# v2.net
KiCad netlist of a schematic drawn in EAGLE
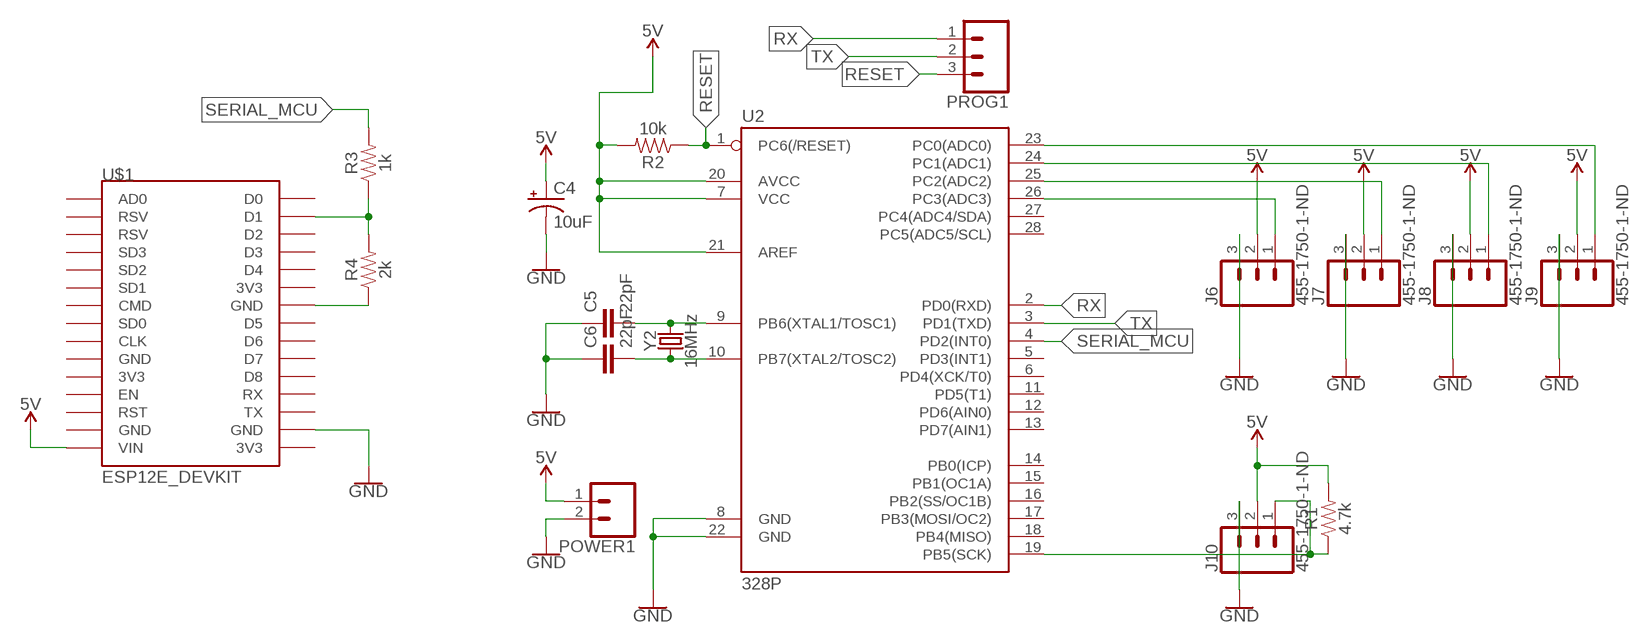
[diagram p0: schematic, sheet 1]

(export (version "E")
  (design (tool "Eeschema 10.0.6"))
  (components
    (comp (ref "C4")
      (value "10uF")
      (footprint "eagle-import:CPOL-RADIAL-2.5MM-5MM")
      (libsource (lib "eagle-import") (part "10UF-POLAR-RADIAL-2.5MM-25V-20%"))
    )
    (comp (ref "C5")
      (value "22pF")
      (footprint "eagle-import:CAP-PTH-2.54")
      (libsource (lib "eagle-import") (part "22PF-PTH-2.54MM-200V-5%"))
    )
    (comp (ref "C6")
      (value "22pF")
      (footprint "eagle-import:CAP-PTH-2.54")
      (libsource (lib "eagle-import") (part "22PF-PTH-2.54MM-200V-5%"))
    )
    (comp (ref "J6")
      (value "455-1750-1-ND")
      (footprint "eagle-import:1X03")
      (libsource (lib "eagle-import") (part "CONN_03"))
    )
    (comp (ref "J7")
      (value "455-1750-1-ND")
      (footprint "eagle-import:1X03")
      (libsource (lib "eagle-import") (part "CONN_03"))
    )
    (comp (ref "J8")
      (value "455-1750-1-ND")
      (footprint "eagle-import:1X03")
      (libsource (lib "eagle-import") (part "CONN_03"))
    )
    (comp (ref "J9")
      (value "455-1750-1-ND")
      (footprint "eagle-import:1X03")
      (libsource (lib "eagle-import") (part "CONN_03"))
    )
    (comp (ref "J10")
      (value "455-1750-1-ND")
      (footprint "eagle-import:1X03")
      (libsource (lib "eagle-import") (part "CONN_03"))
    )
    (comp (ref "POWER1")
      (value "CONN_02")
      (footprint "eagle-import:1X02")
      (libsource (lib "eagle-import") (part "CONN_02"))
    )
    (comp (ref "PROG1")
      (value "CONN_03")
      (footprint "eagle-import:1X03")
      (libsource (lib "eagle-import") (part "SparkFun-Connectors_513_CONN_03"))
    )
    (comp (ref "R1")
      (value "4.7k")
      (footprint "eagle-import:AXIAL-0.3")
      (libsource (lib "eagle-import") (part "10KOHM-HORIZ-1/4W-1%"))
    )
    (comp (ref "R2")
      (value "10k")
      (footprint "eagle-import:AXIAL-0.3")
      (libsource (lib "eagle-import") (part "1KOHM-HORIZ-1/4W-1%"))
    )
    (comp (ref "R3")
      (value "1k")
      (footprint "eagle-import:AXIAL-0.3")
      (libsource (lib "eagle-import") (part "10KOHM-HORIZ-1/4W-1%"))
    )
    (comp (ref "R4")
      (value "2k")
      (footprint "eagle-import:AXIAL-0.3")
      (libsource (lib "eagle-import") (part "10KOHM-HORIZ-1/4W-1%"))
    )
    (comp (ref "U$1")
      (value "ESP12E_DEVKIT")
      (footprint "eagle-import:ESP12E_DEVKIT")
      (libsource (lib "eagle-import") (part "ESP12E_DEVKIT"))
    )
    (comp (ref "U2")
      (value "328P")
      (footprint "eagle-import:DIP28")
      (libsource (lib "eagle-import") (part "ATMEGA328P_PDIP"))
    )
    (comp (ref "Y2")
      (value "16MHz")
      (footprint "eagle-import:HC49US")
      (libsource (lib "eagle-import") (part "CRYSTAL-16MHZPTH-HC49US"))
    )
  )
  (nets
    (net (code "1") (name "5V") (class "Default")
      (node (ref "C4") (pin "1") (pinfunction "+_1") (pintype "passive"))
      (node (ref "J10") (pin "2") (pinfunction "2_2") (pintype "passive"))
      (node (ref "J6") (pin "2") (pinfunction "2_2") (pintype "passive"))
      (node (ref "J7") (pin "2") (pinfunction "2_2") (pintype "passive"))
      (node (ref "J8") (pin "2") (pinfunction "2_2") (pintype "passive"))
      (node (ref "J9") (pin "2") (pinfunction "2_2") (pintype "passive"))
      (node (ref "POWER1") (pin "1") (pinfunction "1_1") (pintype "passive"))
      (node (ref "R1") (pin "P$2") (pinfunction "2_P$2") (pintype "passive"))
      (node (ref "R2") (pin "P$2") (pinfunction "2_P$2") (pintype "passive"))
      (node (ref "U$1") (pin "VIN") (pinfunction "VIN_VIN") (pintype "bidirectional"))
      (node (ref "U2") (pin "20") (pinfunction "AVCC_20") (pintype "bidirectional"))
      (node (ref "U2") (pin "21") (pinfunction "AREF_21") (pintype "bidirectional"))
      (node (ref "U2") (pin "7") (pinfunction "VCC_7") (pintype "bidirectional"))
    )
    (net (code "2") (name "GND") (class "Default")
      (node (ref "C4") (pin "2") (pinfunction "-_2") (pintype "passive"))
      (node (ref "C5") (pin "1") (pinfunction "1_1") (pintype "passive"))
      (node (ref "C6") (pin "1") (pinfunction "1_1") (pintype "passive"))
      (node (ref "J10") (pin "3") (pinfunction "3_3") (pintype "passive"))
      (node (ref "J6") (pin "3") (pinfunction "3_3") (pintype "passive"))
      (node (ref "J7") (pin "3") (pinfunction "3_3") (pintype "passive"))
      (node (ref "J8") (pin "3") (pinfunction "3_3") (pintype "passive"))
      (node (ref "J9") (pin "3") (pinfunction "3_3") (pintype "passive"))
      (node (ref "POWER1") (pin "2") (pinfunction "2_2") (pintype "passive"))
      (node (ref "U$1") (pin "GND@3") (pinfunction "GND_GND@3") (pintype "bidirectional"))
      (node (ref "U2") (pin "22") (pinfunction "GND_22") (pintype "bidirectional"))
      (node (ref "U2") (pin "8") (pinfunction "GND_8") (pintype "bidirectional"))
    )
    (net (code "3") (name "Net-(R1-1)") (class "Default")
      (node (ref "J10") (pin "1") (pinfunction "1_1") (pintype "passive"))
      (node (ref "R1") (pin "P$1") (pinfunction "1_P$1") (pintype "passive"))
      (node (ref "U2") (pin "19") (pinfunction "PB5(SCK)_19") (pintype "bidirectional"))
    )
    (net (code "4") (name "Net-(R3-1)") (class "Default")
      (node (ref "R3") (pin "P$1") (pinfunction "1_P$1") (pintype "passive"))
      (node (ref "R4") (pin "P$2") (pinfunction "2_P$2") (pintype "passive"))
      (node (ref "U$1") (pin "D1") (pinfunction "D1_D1") (pintype "bidirectional"))
    )
    (net (code "5") (name "Net-(R4-1)") (class "Default")
      (node (ref "R4") (pin "P$1") (pinfunction "1_P$1") (pintype "passive"))
      (node (ref "U$1") (pin "GND@2") (pinfunction "GND_GND@2") (pintype "bidirectional"))
    )
    (net (code "6") (name "Net-(U2-PB6(XTAL1{slash}TOSC1))") (class "Default")
      (node (ref "C5") (pin "2") (pinfunction "2_2") (pintype "passive"))
      (node (ref "U2") (pin "9") (pinfunction "PB6(XTAL1/TOSC1)_9") (pintype "bidirectional"))
      (node (ref "Y2") (pin "2") (pinfunction "2_2") (pintype "passive"))
    )
    (net (code "7") (name "Net-(U2-PB7(XTAL2{slash}TOSC2))") (class "Default")
      (node (ref "C6") (pin "2") (pinfunction "2_2") (pintype "passive"))
      (node (ref "U2") (pin "10") (pinfunction "PB7(XTAL2/TOSC2)_10") (pintype "bidirectional"))
      (node (ref "Y2") (pin "1") (pinfunction "1_1") (pintype "passive"))
    )
    (net (code "8") (name "Net-(U2-PC0(ADC0))") (class "Default")
      (node (ref "J9") (pin "1") (pinfunction "1_1") (pintype "passive"))
      (node (ref "U2") (pin "23") (pinfunction "PC0(ADC0)_23") (pintype "bidirectional"))
    )
    (net (code "9") (name "Net-(U2-PC1(ADC1))") (class "Default")
      (node (ref "J8") (pin "1") (pinfunction "1_1") (pintype "passive"))
      (node (ref "U2") (pin "24") (pinfunction "PC1(ADC1)_24") (pintype "bidirectional"))
    )
    (net (code "10") (name "Net-(U2-PC2(ADC2))") (class "Default")
      (node (ref "J7") (pin "1") (pinfunction "1_1") (pintype "passive"))
      (node (ref "U2") (pin "25") (pinfunction "PC2(ADC2)_25") (pintype "bidirectional"))
    )
    (net (code "11") (name "Net-(U2-PC3(ADC3))") (class "Default")
      (node (ref "J6") (pin "1") (pinfunction "1_1") (pintype "passive"))
      (node (ref "U2") (pin "26") (pinfunction "PC3(ADC3)_26") (pintype "bidirectional"))
    )
    (net (code "12") (name "RESET") (class "Default")
      (node (ref "PROG1") (pin "3") (pinfunction "3_3") (pintype "passive"))
      (node (ref "R2") (pin "P$1") (pinfunction "1_P$1") (pintype "passive"))
      (node (ref "U2") (pin "1") (pinfunction "PC6(/RESET)_1") (pintype "bidirectional"))
    )
    (net (code "13") (name "RX") (class "Default")
      (node (ref "PROG1") (pin "1") (pinfunction "1_1") (pintype "passive"))
      (node (ref "U2") (pin "2") (pinfunction "PD0(RXD)_2") (pintype "bidirectional"))
    )
    (net (code "14") (name "SERIAL_MCU") (class "Default")
      (node (ref "R3") (pin "P$2") (pinfunction "2_P$2") (pintype "passive"))
      (node (ref "U2") (pin "4") (pinfunction "PD2(INT0)_4") (pintype "bidirectional"))
    )
    (net (code "15") (name "TX") (class "Default")
      (node (ref "PROG1") (pin "2") (pinfunction "2_2") (pintype "passive"))
      (node (ref "U2") (pin "3") (pinfunction "PD1(TXD)_3") (pintype "bidirectional"))
    )
    (net (code "16") (name "unconnected-(U$1-3V3-Pad3V3@0)") (class "Default")
      (node (ref "U$1") (pin "3V3@0") (pinfunction "3V3_3V3@0") (pintype "bidirectional"))
    )
    (net (code "17") (name "unconnected-(U$1-3V3-Pad3V3@1)") (class "Default")
      (node (ref "U$1") (pin "3V3@1") (pinfunction "3V3_3V3@1") (pintype "bidirectional"))
    )
    (net (code "18") (name "unconnected-(U$1-3V3-Pad3V3@2)") (class "Default")
      (node (ref "U$1") (pin "3V3@2") (pinfunction "3V3_3V3@2") (pintype "bidirectional"))
    )
    (net (code "19") (name "unconnected-(U$1-GND-PadGND@0)") (class "Default")
      (node (ref "U$1") (pin "GND@0") (pinfunction "GND_GND@0") (pintype "bidirectional"))
    )
    (net (code "20") (name "unconnected-(U$1-GND-PadGND@1)") (class "Default")
      (node (ref "U$1") (pin "GND@1") (pinfunction "GND_GND@1") (pintype "bidirectional"))
    )
    (net (code "21") (name "unconnected-(U$1-PadAD0)") (class "Default")
      (node (ref "U$1") (pin "AD0") (pinfunction "AD0_AD0") (pintype "bidirectional"))
    )
    (net (code "22") (name "unconnected-(U$1-PadCLK)") (class "Default")
      (node (ref "U$1") (pin "CLK") (pinfunction "CLK_CLK") (pintype "bidirectional"))
    )
    (net (code "23") (name "unconnected-(U$1-PadCMD)") (class "Default")
      (node (ref "U$1") (pin "CMD") (pinfunction "CMD_CMD") (pintype "bidirectional"))
    )
    (net (code "24") (name "unconnected-(U$1-PadD0)") (class "Default")
      (node (ref "U$1") (pin "D0") (pinfunction "D0_D0") (pintype "bidirectional"))
    )
    (net (code "25") (name "unconnected-(U$1-PadD2)") (class "Default")
      (node (ref "U$1") (pin "D2") (pinfunction "D2_D2") (pintype "bidirectional"))
    )
    (net (code "26") (name "unconnected-(U$1-PadD3)") (class "Default")
      (node (ref "U$1") (pin "D3") (pinfunction "D3_D3") (pintype "bidirectional"))
    )
    (net (code "27") (name "unconnected-(U$1-PadD4)") (class "Default")
      (node (ref "U$1") (pin "D4") (pinfunction "D4_D4") (pintype "bidirectional"))
    )
    (net (code "28") (name "unconnected-(U$1-PadD5)") (class "Default")
      (node (ref "U$1") (pin "D5") (pinfunction "D5_D5") (pintype "bidirectional"))
    )
    (net (code "29") (name "unconnected-(U$1-PadD6)") (class "Default")
      (node (ref "U$1") (pin "D6") (pinfunction "D6_D6") (pintype "bidirectional"))
    )
    (net (code "30") (name "unconnected-(U$1-PadD7)") (class "Default")
      (node (ref "U$1") (pin "D7") (pinfunction "D7_D7") (pintype "bidirectional"))
    )
    (net (code "31") (name "unconnected-(U$1-PadD8)") (class "Default")
      (node (ref "U$1") (pin "D8") (pinfunction "D8_D8") (pintype "bidirectional"))
    )
    (net (code "32") (name "unconnected-(U$1-PadEN)") (class "Default")
      (node (ref "U$1") (pin "EN") (pinfunction "EN_EN") (pintype "bidirectional"))
    )
    (net (code "33") (name "unconnected-(U$1-PadRST)") (class "Default")
      (node (ref "U$1") (pin "RST") (pinfunction "RST_RST") (pintype "bidirectional"))
    )
    (net (code "34") (name "unconnected-(U$1-PadRX)") (class "Default")
      (node (ref "U$1") (pin "RX") (pinfunction "RX_RX") (pintype "bidirectional"))
    )
    (net (code "35") (name "unconnected-(U$1-PadSD0)") (class "Default")
      (node (ref "U$1") (pin "SD0") (pinfunction "SD0_SD0") (pintype "bidirectional"))
    )
    (net (code "36") (name "unconnected-(U$1-PadSD1)") (class "Default")
      (node (ref "U$1") (pin "SD1") (pinfunction "SD1_SD1") (pintype "bidirectional"))
    )
    (net (code "37") (name "unconnected-(U$1-PadSD2)") (class "Default")
      (node (ref "U$1") (pin "SD2") (pinfunction "SD2_SD2") (pintype "bidirectional"))
    )
    (net (code "38") (name "unconnected-(U$1-PadSD3)") (class "Default")
      (node (ref "U$1") (pin "SD3") (pinfunction "SD3_SD3") (pintype "bidirectional"))
    )
    (net (code "39") (name "unconnected-(U$1-PadTX)") (class "Default")
      (node (ref "U$1") (pin "TX") (pinfunction "TX_TX") (pintype "bidirectional"))
    )
    (net (code "40") (name "unconnected-(U$1-RSV-PadRSV@0)") (class "Default")
      (node (ref "U$1") (pin "RSV@0") (pinfunction "RSV_RSV@0") (pintype "bidirectional"))
    )
    (net (code "41") (name "unconnected-(U$1-RSV-PadRSV@1)") (class "Default")
      (node (ref "U$1") (pin "RSV@1") (pinfunction "RSV_RSV@1") (pintype "bidirectional"))
    )
    (net (code "42") (name "unconnected-(U2-PB0(ICP)-Pad14)") (class "Default")
      (node (ref "U2") (pin "14") (pinfunction "PB0(ICP)_14") (pintype "bidirectional"))
    )
    (net (code "43") (name "unconnected-(U2-PB1(OC1A)-Pad15)") (class "Default")
      (node (ref "U2") (pin "15") (pinfunction "PB1(OC1A)_15") (pintype "bidirectional"))
    )
    (net (code "44") (name "unconnected-(U2-PB2(SS{slash}OC1B)-Pad16)") (class "Default")
      (node (ref "U2") (pin "16") (pinfunction "PB2(SS/OC1B)_16") (pintype "bidirectional"))
    )
    (net (code "45") (name "unconnected-(U2-PB3(MOSI{slash}OC2)-Pad17)") (class "Default")
      (node (ref "U2") (pin "17") (pinfunction "PB3(MOSI/OC2)_17") (pintype "bidirectional"))
    )
    (net (code "46") (name "unconnected-(U2-PB4(MISO)-Pad18)") (class "Default")
      (node (ref "U2") (pin "18") (pinfunction "PB4(MISO)_18") (pintype "bidirectional"))
    )
    (net (code "47") (name "unconnected-(U2-PC4(ADC4{slash}SDA)-Pad27)") (class "Default")
      (node (ref "U2") (pin "27") (pinfunction "PC4(ADC4/SDA)_27") (pintype "bidirectional"))
    )
    (net (code "48") (name "unconnected-(U2-PC5(ADC5{slash}SCL)-Pad28)") (class "Default")
      (node (ref "U2") (pin "28") (pinfunction "PC5(ADC5/SCL)_28") (pintype "bidirectional"))
    )
    (net (code "49") (name "unconnected-(U2-PD3(INT1)-Pad5)") (class "Default")
      (node (ref "U2") (pin "5") (pinfunction "PD3(INT1)_5") (pintype "bidirectional"))
    )
    (net (code "50") (name "unconnected-(U2-PD4(XCK{slash}T0)-Pad6)") (class "Default")
      (node (ref "U2") (pin "6") (pinfunction "PD4(XCK/T0)_6") (pintype "bidirectional"))
    )
    (net (code "51") (name "unconnected-(U2-PD5(T1)-Pad11)") (class "Default")
      (node (ref "U2") (pin "11") (pinfunction "PD5(T1)_11") (pintype "bidirectional"))
    )
    (net (code "52") (name "unconnected-(U2-PD6(AIN0)-Pad12)") (class "Default")
      (node (ref "U2") (pin "12") (pinfunction "PD6(AIN0)_12") (pintype "bidirectional"))
    )
    (net (code "53") (name "unconnected-(U2-PD7(AIN1)-Pad13)") (class "Default")
      (node (ref "U2") (pin "13") (pinfunction "PD7(AIN1)_13") (pintype "bidirectional"))
    )
  )
)
